# 74FCT3807S_PINOUT.net
KiCad netlist of a schematic drawn in Altium Designer
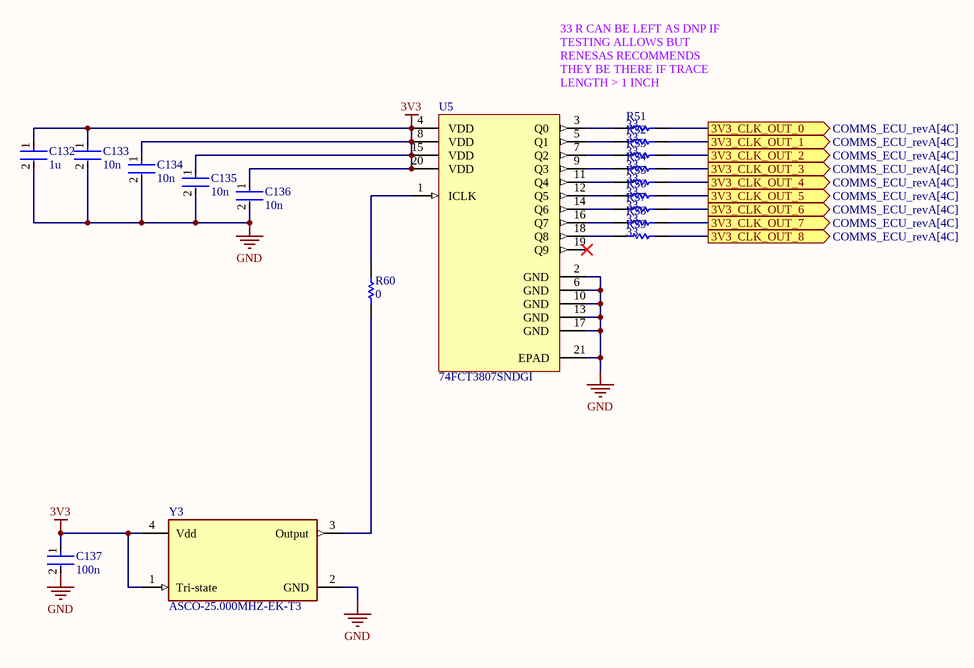
[diagram p0: 74FCT3807S_PINOUT.SchDoc]

(export (version "E")
  (design (tool "Eeschema 10.0.6"))
  (components
    (comp (ref "C132")
      (value "1u")
      (footprint "FP-0402-L_1_0_0_05-W_0_5-IPC_A")
      (description "LARGE PADS, 0402 CAP, CHANGE COMMENT TO MATCH REAL P/N")
      (libsource (lib "Space Concordia") (part "b4654b650e69147ec39a6b967a45e02"))
    )
    (comp (ref "C133")
      (value "10n")
      (footprint "FP-0402-L_1_0_0_05-W_0_5-IPC_A")
      (description "LARGE PADS, 0402 CAP, CHANGE COMMENT TO MATCH REAL P/N")
      (libsource (lib "Space Concordia") (part "b4654b650e69147ec39a6b967a45e02"))
    )
    (comp (ref "C134")
      (value "10n")
      (footprint "FP-0402-L_1_0_0_05-W_0_5-IPC_A")
      (description "LARGE PADS, 0402 CAP, CHANGE COMMENT TO MATCH REAL P/N")
      (libsource (lib "Space Concordia") (part "b4654b650e69147ec39a6b967a45e02"))
    )
    (comp (ref "C135")
      (value "10n")
      (footprint "FP-0402-L_1_0_0_05-W_0_5-IPC_A")
      (description "LARGE PADS, 0402 CAP, CHANGE COMMENT TO MATCH REAL P/N")
      (libsource (lib "Space Concordia") (part "b4654b650e69147ec39a6b967a45e02"))
    )
    (comp (ref "C136")
      (value "10n")
      (footprint "FP-0402-L_1_0_0_05-W_0_5-IPC_A")
      (description "LARGE PADS, 0402 CAP, CHANGE COMMENT TO MATCH REAL P/N")
      (libsource (lib "Space Concordia") (part "b4654b650e69147ec39a6b967a45e02"))
    )
    (comp (ref "C137")
      (value "100n")
      (footprint "FP-0402-L_1_0_0_05-W_0_5-IPC_A")
      (description "LARGE PADS, 0402 CAP, CHANGE COMMENT TO MATCH REAL P/N")
      (libsource (lib "Space Concordia") (part "b4654b650e69147ec39a6b967a45e02"))
    )
    (comp (ref "R51")
      (value "33")
      (footprint "RESC1005X40X25ML05T05")
      (description "READ THE NAME")
      (libsource (lib "Space Concordia") (part "CMP-009-00206-2"))
    )
    (comp (ref "R52")
      (value "33")
      (footprint "RESC1005X40X25ML05T05")
      (description "READ THE NAME")
      (libsource (lib "Space Concordia") (part "CMP-009-00206-2"))
    )
    (comp (ref "R53")
      (value "33")
      (footprint "RESC1005X40X25ML05T05")
      (description "READ THE NAME")
      (libsource (lib "Space Concordia") (part "CMP-009-00206-2"))
    )
    (comp (ref "R54")
      (value "33")
      (footprint "RESC1005X40X25ML05T05")
      (description "READ THE NAME")
      (libsource (lib "Space Concordia") (part "CMP-009-00206-2"))
    )
    (comp (ref "R55")
      (value "33")
      (footprint "RESC1005X40X25ML05T05")
      (description "READ THE NAME")
      (libsource (lib "Space Concordia") (part "CMP-009-00206-2"))
    )
    (comp (ref "R56")
      (value "33")
      (footprint "RESC1005X40X25ML05T05")
      (description "READ THE NAME")
      (libsource (lib "Space Concordia") (part "CMP-009-00206-2"))
    )
    (comp (ref "R57")
      (value "33")
      (footprint "RESC1005X40X25ML05T05")
      (description "READ THE NAME")
      (libsource (lib "Space Concordia") (part "CMP-009-00206-2"))
    )
    (comp (ref "R58")
      (value "33")
      (footprint "RESC1005X40X25ML05T05")
      (description "READ THE NAME")
      (libsource (lib "Space Concordia") (part "CMP-009-00206-2"))
    )
    (comp (ref "R59")
      (value "33")
      (footprint "RESC1005X40X25ML05T05")
      (description "READ THE NAME")
      (libsource (lib "Space Concordia") (part "CMP-009-00206-2"))
    )
    (comp (ref "R60")
      (value "0")
      (footprint "RESC1005X40X25ML05T05")
      (description "READ THE NAME")
      (libsource (lib "Space Concordia") (part "CMP-009-00206-2"))
    )
    (comp (ref "U5")
      (value "74FCT3807SNDGI")
      (footprint "NDG20S2_MFG")
      (description "Clock Fanout Buffer (Distribution) IC 110 200 MHz 20-VFQFN Exposed Pad")
      (libsource (lib "Altium Content Vault") (part "0537f4cd8e5bda7646e6b4ef6da9717"))
    )
    (comp (ref "Y3")
      (value "ASCO-25.000MHZ-EK-T3")
      (footprint "FP-ASCO-MFG")
      (description "XTAL OSC XO 25.0000MHZ CMOS SMD")
      (libsource (lib "Altium Content Vault") (part "7fe67d64e7d3fcf9859fbced3acf591"))
    )
  )
  (nets
    (net (code "1") (name "/3V3_CLK_OUT_0") (class "Default")
      (node (ref "R51") (pin "2") (pinfunction "2_2") (pintype "passive"))
    )
    (net (code "2") (name "/3V3_CLK_OUT_1") (class "Default")
      (node (ref "R52") (pin "2") (pinfunction "2_2") (pintype "passive"))
    )
    (net (code "3") (name "/3V3_CLK_OUT_2") (class "Default")
      (node (ref "R53") (pin "2") (pinfunction "2_2") (pintype "passive"))
    )
    (net (code "4") (name "/3V3_CLK_OUT_3") (class "Default")
      (node (ref "R54") (pin "2") (pinfunction "2_2") (pintype "passive"))
    )
    (net (code "5") (name "/3V3_CLK_OUT_4") (class "Default")
      (node (ref "R55") (pin "2") (pinfunction "2_2") (pintype "passive"))
    )
    (net (code "6") (name "/3V3_CLK_OUT_5") (class "Default")
      (node (ref "R56") (pin "2") (pinfunction "2_2") (pintype "passive"))
    )
    (net (code "7") (name "/3V3_CLK_OUT_6") (class "Default")
      (node (ref "R57") (pin "2") (pinfunction "2_2") (pintype "passive"))
    )
    (net (code "8") (name "/3V3_CLK_OUT_7") (class "Default")
      (node (ref "R58") (pin "2") (pinfunction "2_2") (pintype "passive"))
    )
    (net (code "9") (name "/3V3_CLK_OUT_8") (class "Default")
      (node (ref "R59") (pin "2") (pinfunction "2_2") (pintype "passive"))
    )
    (net (code "10") (name "3V3") (class "Default")
      (node (ref "C132") (pin "1") (pinfunction "1_1") (pintype "passive"))
      (node (ref "C133") (pin "1") (pinfunction "1_1") (pintype "passive"))
      (node (ref "C134") (pin "1") (pinfunction "1_1") (pintype "passive"))
      (node (ref "C135") (pin "1") (pinfunction "1_1") (pintype "passive"))
      (node (ref "C136") (pin "1") (pinfunction "1_1") (pintype "passive"))
      (node (ref "C137") (pin "1") (pinfunction "1_1") (pintype "passive"))
      (node (ref "U5") (pin "15") (pinfunction "VDD_15") (pintype "power_in"))
      (node (ref "U5") (pin "20") (pinfunction "VDD_20") (pintype "power_in"))
      (node (ref "U5") (pin "4") (pinfunction "VDD_4") (pintype "power_in"))
      (node (ref "U5") (pin "8") (pinfunction "VDD_8") (pintype "power_in"))
      (node (ref "Y3") (pin "1") (pinfunction "Tri-state_1") (pintype "input"))
      (node (ref "Y3") (pin "4") (pinfunction "Vdd_4") (pintype "power_in"))
    )
    (net (code "11") (name "GND") (class "Default")
      (node (ref "C132") (pin "2") (pinfunction "2_2") (pintype "passive"))
      (node (ref "C133") (pin "2") (pinfunction "2_2") (pintype "passive"))
      (node (ref "C134") (pin "2") (pinfunction "2_2") (pintype "passive"))
      (node (ref "C135") (pin "2") (pinfunction "2_2") (pintype "passive"))
      (node (ref "C136") (pin "2") (pinfunction "2_2") (pintype "passive"))
      (node (ref "C137") (pin "2") (pinfunction "2_2") (pintype "passive"))
      (node (ref "U5") (pin "10") (pinfunction "GND_10") (pintype "power_in"))
      (node (ref "U5") (pin "13") (pinfunction "GND_13") (pintype "power_in"))
      (node (ref "U5") (pin "17") (pinfunction "GND_17") (pintype "power_in"))
      (node (ref "U5") (pin "2") (pinfunction "GND_2") (pintype "power_in"))
      (node (ref "U5") (pin "21") (pinfunction "EPAD_21") (pintype "power_in"))
      (node (ref "U5") (pin "6") (pinfunction "GND_6") (pintype "power_in"))
      (node (ref "Y3") (pin "2") (pinfunction "GND_2") (pintype "power_in"))
    )
    (net (code "12") (name "Net-(U5-ICLK)") (class "Default")
      (node (ref "R60") (pin "2") (pinfunction "2_2") (pintype "passive"))
      (node (ref "U5") (pin "1") (pinfunction "ICLK_1") (pintype "input"))
    )
    (net (code "13") (name "Net-(U5-Q0)") (class "Default")
      (node (ref "R51") (pin "1") (pinfunction "1_1") (pintype "passive"))
      (node (ref "U5") (pin "3") (pinfunction "Q0_3") (pintype "output"))
    )
    (net (code "14") (name "Net-(U5-Q1)") (class "Default")
      (node (ref "R52") (pin "1") (pinfunction "1_1") (pintype "passive"))
      (node (ref "U5") (pin "5") (pinfunction "Q1_5") (pintype "output"))
    )
    (net (code "15") (name "Net-(U5-Q2)") (class "Default")
      (node (ref "R53") (pin "1") (pinfunction "1_1") (pintype "passive"))
      (node (ref "U5") (pin "7") (pinfunction "Q2_7") (pintype "output"))
    )
    (net (code "16") (name "Net-(U5-Q3)") (class "Default")
      (node (ref "R54") (pin "1") (pinfunction "1_1") (pintype "passive"))
      (node (ref "U5") (pin "9") (pinfunction "Q3_9") (pintype "output"))
    )
    (net (code "17") (name "Net-(U5-Q4)") (class "Default")
      (node (ref "R55") (pin "1") (pinfunction "1_1") (pintype "passive"))
      (node (ref "U5") (pin "11") (pinfunction "Q4_11") (pintype "output"))
    )
    (net (code "18") (name "Net-(U5-Q5)") (class "Default")
      (node (ref "R56") (pin "1") (pinfunction "1_1") (pintype "passive"))
      (node (ref "U5") (pin "12") (pinfunction "Q5_12") (pintype "output"))
    )
    (net (code "19") (name "Net-(U5-Q6)") (class "Default")
      (node (ref "R57") (pin "1") (pinfunction "1_1") (pintype "passive"))
      (node (ref "U5") (pin "14") (pinfunction "Q6_14") (pintype "output"))
    )
    (net (code "20") (name "Net-(U5-Q7)") (class "Default")
      (node (ref "R58") (pin "1") (pinfunction "1_1") (pintype "passive"))
      (node (ref "U5") (pin "16") (pinfunction "Q7_16") (pintype "output"))
    )
    (net (code "21") (name "Net-(U5-Q8)") (class "Default")
      (node (ref "R59") (pin "1") (pinfunction "1_1") (pintype "passive"))
      (node (ref "U5") (pin "18") (pinfunction "Q8_18") (pintype "output"))
    )
    (net (code "22") (name "Net-(Y3-Output)") (class "Default")
      (node (ref "R60") (pin "1") (pinfunction "1_1") (pintype "passive"))
      (node (ref "Y3") (pin "3") (pinfunction "Output_3") (pintype "output"))
    )
    (net (code "23") (name "unconnected-(U5-Q9-Pad19)") (class "Default")
      (node (ref "U5") (pin "19") (pinfunction "Q9_19") (pintype "output+no_connect"))
    )
  )
)
